# 3-8.net
KiCad netlist of a schematic drawn in Altium Designer
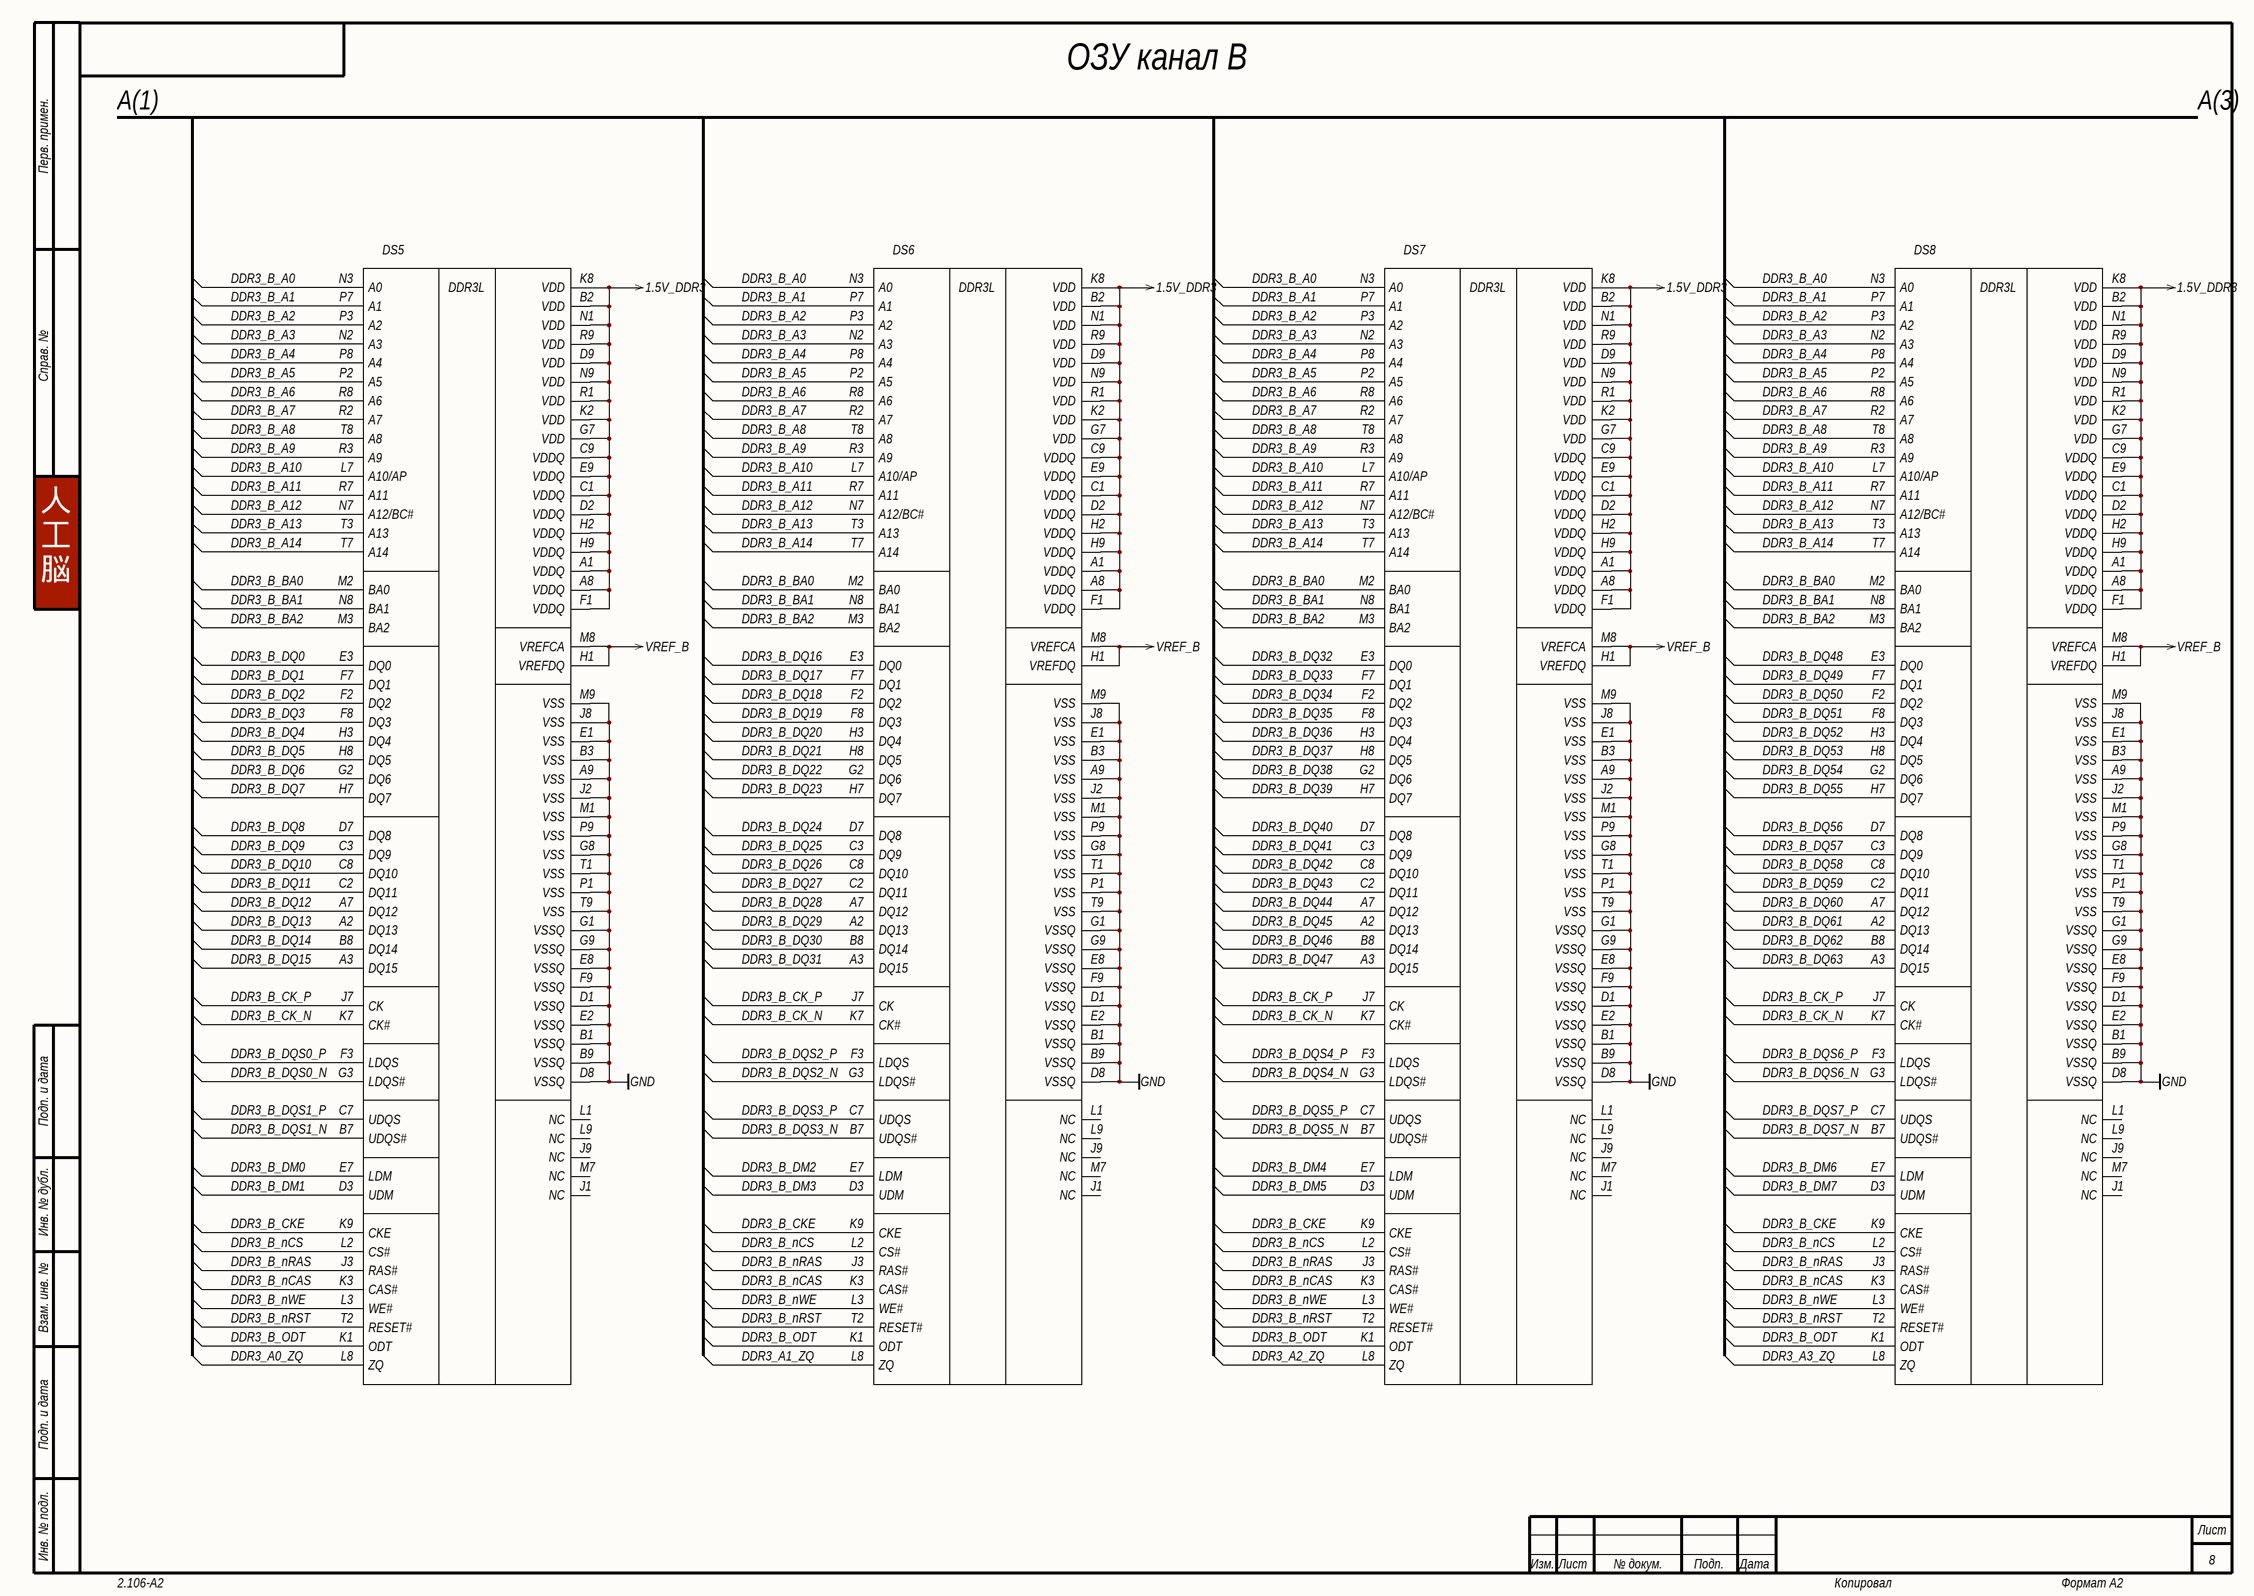
[diagram p0: Э3-8.SchDoc]

(export (version "E")
  (design (tool "Eeschema 10.0.6"))
  (components
    (comp (ref "DS5")
      (value "1")
      (footprint "96-FBGA")
      (description "32 Megx16x8 banks DDR3L SDRAM")
      (fields (field (name "MANUFACTURER") "Micron Technology, Inc."))
      (libsource (lib "Digital") (part "MT41K256M16TW-107IT{colon}P"))
    )
    (comp (ref "DS6")
      (value "1")
      (footprint "96-FBGA")
      (description "32 Megx16x8 banks DDR3L SDRAM")
      (fields (field (name "MANUFACTURER") "Micron Technology, Inc."))
      (libsource (lib "Digital") (part "MT41K256M16TW-107IT{colon}P"))
    )
    (comp (ref "DS7")
      (value "1")
      (footprint "96-FBGA")
      (description "32 Megx16x8 banks DDR3L SDRAM")
      (fields (field (name "MANUFACTURER") "Micron Technology, Inc."))
      (libsource (lib "Digital") (part "MT41K256M16TW-107IT{colon}P"))
    )
    (comp (ref "DS8")
      (value "1")
      (footprint "96-FBGA")
      (description "32 Megx16x8 banks DDR3L SDRAM")
      (fields (field (name "MANUFACTURER") "Micron Technology, Inc."))
      (libsource (lib "Digital") (part "MT41K256M16TW-107IT{colon}P"))
    )
  )
  (nets
    (net (code "1") (name "/DDR3_A0_ZQ") (class "Default")
      (node (ref "DS5") (pin "L8") (pinfunction "ZQ_L8") (pintype "passive"))
    )
    (net (code "2") (name "/DDR3_A1_ZQ") (class "Default")
      (node (ref "DS6") (pin "L8") (pinfunction "ZQ_L8") (pintype "passive"))
    )
    (net (code "3") (name "/DDR3_A2_ZQ") (class "Default")
      (node (ref "DS7") (pin "L8") (pinfunction "ZQ_L8") (pintype "passive"))
    )
    (net (code "4") (name "/DDR3_A3_ZQ") (class "Default")
      (node (ref "DS8") (pin "L8") (pinfunction "ZQ_L8") (pintype "passive"))
    )
    (net (code "5") (name "/DDR3_B_A0") (class "Default")
      (node (ref "DS5") (pin "N3") (pinfunction "A0_N3") (pintype "passive"))
      (node (ref "DS6") (pin "N3") (pinfunction "A0_N3") (pintype "passive"))
      (node (ref "DS7") (pin "N3") (pinfunction "A0_N3") (pintype "passive"))
      (node (ref "DS8") (pin "N3") (pinfunction "A0_N3") (pintype "passive"))
    )
    (net (code "6") (name "/DDR3_B_A1") (class "Default")
      (node (ref "DS5") (pin "P7") (pinfunction "A1_P7") (pintype "passive"))
      (node (ref "DS6") (pin "P7") (pinfunction "A1_P7") (pintype "passive"))
      (node (ref "DS7") (pin "P7") (pinfunction "A1_P7") (pintype "passive"))
      (node (ref "DS8") (pin "P7") (pinfunction "A1_P7") (pintype "passive"))
    )
    (net (code "7") (name "/DDR3_B_A2") (class "Default")
      (node (ref "DS5") (pin "P3") (pinfunction "A2_P3") (pintype "passive"))
      (node (ref "DS6") (pin "P3") (pinfunction "A2_P3") (pintype "passive"))
      (node (ref "DS7") (pin "P3") (pinfunction "A2_P3") (pintype "passive"))
      (node (ref "DS8") (pin "P3") (pinfunction "A2_P3") (pintype "passive"))
    )
    (net (code "8") (name "/DDR3_B_A3") (class "Default")
      (node (ref "DS5") (pin "N2") (pinfunction "A3_N2") (pintype "passive"))
      (node (ref "DS6") (pin "N2") (pinfunction "A3_N2") (pintype "passive"))
      (node (ref "DS7") (pin "N2") (pinfunction "A3_N2") (pintype "passive"))
      (node (ref "DS8") (pin "N2") (pinfunction "A3_N2") (pintype "passive"))
    )
    (net (code "9") (name "/DDR3_B_A4") (class "Default")
      (node (ref "DS5") (pin "P8") (pinfunction "A4_P8") (pintype "passive"))
      (node (ref "DS6") (pin "P8") (pinfunction "A4_P8") (pintype "passive"))
      (node (ref "DS7") (pin "P8") (pinfunction "A4_P8") (pintype "passive"))
      (node (ref "DS8") (pin "P8") (pinfunction "A4_P8") (pintype "passive"))
    )
    (net (code "10") (name "/DDR3_B_A5") (class "Default")
      (node (ref "DS5") (pin "P2") (pinfunction "A5_P2") (pintype "passive"))
      (node (ref "DS6") (pin "P2") (pinfunction "A5_P2") (pintype "passive"))
      (node (ref "DS7") (pin "P2") (pinfunction "A5_P2") (pintype "passive"))
      (node (ref "DS8") (pin "P2") (pinfunction "A5_P2") (pintype "passive"))
    )
    (net (code "11") (name "/DDR3_B_A6") (class "Default")
      (node (ref "DS5") (pin "R8") (pinfunction "A6_R8") (pintype "passive"))
      (node (ref "DS6") (pin "R8") (pinfunction "A6_R8") (pintype "passive"))
      (node (ref "DS7") (pin "R8") (pinfunction "A6_R8") (pintype "passive"))
      (node (ref "DS8") (pin "R8") (pinfunction "A6_R8") (pintype "passive"))
    )
    (net (code "12") (name "/DDR3_B_A7") (class "Default")
      (node (ref "DS5") (pin "R2") (pinfunction "A7_R2") (pintype "passive"))
      (node (ref "DS6") (pin "R2") (pinfunction "A7_R2") (pintype "passive"))
      (node (ref "DS7") (pin "R2") (pinfunction "A7_R2") (pintype "passive"))
      (node (ref "DS8") (pin "R2") (pinfunction "A7_R2") (pintype "passive"))
    )
    (net (code "13") (name "/DDR3_B_A8") (class "Default")
      (node (ref "DS5") (pin "T8") (pinfunction "A8_T8") (pintype "passive"))
      (node (ref "DS6") (pin "T8") (pinfunction "A8_T8") (pintype "passive"))
      (node (ref "DS7") (pin "T8") (pinfunction "A8_T8") (pintype "passive"))
      (node (ref "DS8") (pin "T8") (pinfunction "A8_T8") (pintype "passive"))
    )
    (net (code "14") (name "/DDR3_B_A9") (class "Default")
      (node (ref "DS5") (pin "R3") (pinfunction "A9_R3") (pintype "passive"))
      (node (ref "DS6") (pin "R3") (pinfunction "A9_R3") (pintype "passive"))
      (node (ref "DS7") (pin "R3") (pinfunction "A9_R3") (pintype "passive"))
      (node (ref "DS8") (pin "R3") (pinfunction "A9_R3") (pintype "passive"))
    )
    (net (code "15") (name "/DDR3_B_A10") (class "Default")
      (node (ref "DS5") (pin "L7") (pinfunction "A10/AP_L7") (pintype "passive"))
      (node (ref "DS6") (pin "L7") (pinfunction "A10/AP_L7") (pintype "passive"))
      (node (ref "DS7") (pin "L7") (pinfunction "A10/AP_L7") (pintype "passive"))
      (node (ref "DS8") (pin "L7") (pinfunction "A10/AP_L7") (pintype "passive"))
    )
    (net (code "16") (name "/DDR3_B_A11") (class "Default")
      (node (ref "DS5") (pin "R7") (pinfunction "A11_R7") (pintype "passive"))
      (node (ref "DS6") (pin "R7") (pinfunction "A11_R7") (pintype "passive"))
      (node (ref "DS7") (pin "R7") (pinfunction "A11_R7") (pintype "passive"))
      (node (ref "DS8") (pin "R7") (pinfunction "A11_R7") (pintype "passive"))
    )
    (net (code "17") (name "/DDR3_B_A12") (class "Default")
      (node (ref "DS5") (pin "N7") (pinfunction "A12/BC#_N7") (pintype "passive"))
      (node (ref "DS6") (pin "N7") (pinfunction "A12/BC#_N7") (pintype "passive"))
      (node (ref "DS7") (pin "N7") (pinfunction "A12/BC#_N7") (pintype "passive"))
      (node (ref "DS8") (pin "N7") (pinfunction "A12/BC#_N7") (pintype "passive"))
    )
    (net (code "18") (name "/DDR3_B_A13") (class "Default")
      (node (ref "DS5") (pin "T3") (pinfunction "A13_T3") (pintype "passive"))
      (node (ref "DS6") (pin "T3") (pinfunction "A13_T3") (pintype "passive"))
      (node (ref "DS7") (pin "T3") (pinfunction "A13_T3") (pintype "passive"))
      (node (ref "DS8") (pin "T3") (pinfunction "A13_T3") (pintype "passive"))
    )
    (net (code "19") (name "/DDR3_B_A14") (class "Default")
      (node (ref "DS5") (pin "T7") (pinfunction "A14_T7") (pintype "passive"))
      (node (ref "DS6") (pin "T7") (pinfunction "A14_T7") (pintype "passive"))
      (node (ref "DS7") (pin "T7") (pinfunction "A14_T7") (pintype "passive"))
      (node (ref "DS8") (pin "T7") (pinfunction "A14_T7") (pintype "passive"))
    )
    (net (code "20") (name "/DDR3_B_BA0") (class "Default")
      (node (ref "DS5") (pin "M2") (pinfunction "BA0_M2") (pintype "passive"))
      (node (ref "DS6") (pin "M2") (pinfunction "BA0_M2") (pintype "passive"))
      (node (ref "DS7") (pin "M2") (pinfunction "BA0_M2") (pintype "passive"))
      (node (ref "DS8") (pin "M2") (pinfunction "BA0_M2") (pintype "passive"))
    )
    (net (code "21") (name "/DDR3_B_BA1") (class "Default")
      (node (ref "DS5") (pin "N8") (pinfunction "BA1_N8") (pintype "passive"))
      (node (ref "DS6") (pin "N8") (pinfunction "BA1_N8") (pintype "passive"))
      (node (ref "DS7") (pin "N8") (pinfunction "BA1_N8") (pintype "passive"))
      (node (ref "DS8") (pin "N8") (pinfunction "BA1_N8") (pintype "passive"))
    )
    (net (code "22") (name "/DDR3_B_BA2") (class "Default")
      (node (ref "DS5") (pin "M3") (pinfunction "BA2_M3") (pintype "passive"))
      (node (ref "DS6") (pin "M3") (pinfunction "BA2_M3") (pintype "passive"))
      (node (ref "DS7") (pin "M3") (pinfunction "BA2_M3") (pintype "passive"))
      (node (ref "DS8") (pin "M3") (pinfunction "BA2_M3") (pintype "passive"))
    )
    (net (code "23") (name "/DDR3_B_CKE") (class "Default")
      (node (ref "DS5") (pin "K9") (pinfunction "CKE_K9") (pintype "passive"))
      (node (ref "DS6") (pin "K9") (pinfunction "CKE_K9") (pintype "passive"))
      (node (ref "DS7") (pin "K9") (pinfunction "CKE_K9") (pintype "passive"))
      (node (ref "DS8") (pin "K9") (pinfunction "CKE_K9") (pintype "passive"))
    )
    (net (code "24") (name "/DDR3_B_CK_N") (class "Default")
      (node (ref "DS5") (pin "K7") (pinfunction "CK#_K7") (pintype "passive"))
      (node (ref "DS6") (pin "K7") (pinfunction "CK#_K7") (pintype "passive"))
      (node (ref "DS7") (pin "K7") (pinfunction "CK#_K7") (pintype "passive"))
      (node (ref "DS8") (pin "K7") (pinfunction "CK#_K7") (pintype "passive"))
    )
    (net (code "25") (name "/DDR3_B_CK_P") (class "Default")
      (node (ref "DS5") (pin "J7") (pinfunction "CK_J7") (pintype "passive"))
      (node (ref "DS6") (pin "J7") (pinfunction "CK_J7") (pintype "passive"))
      (node (ref "DS7") (pin "J7") (pinfunction "CK_J7") (pintype "passive"))
      (node (ref "DS8") (pin "J7") (pinfunction "CK_J7") (pintype "passive"))
    )
    (net (code "26") (name "/DDR3_B_DM0") (class "Default")
      (node (ref "DS5") (pin "E7") (pinfunction "LDM_E7") (pintype "passive"))
    )
    (net (code "27") (name "/DDR3_B_DM1") (class "Default")
      (node (ref "DS5") (pin "D3") (pinfunction "UDM_D3") (pintype "passive"))
    )
    (net (code "28") (name "/DDR3_B_DM2") (class "Default")
      (node (ref "DS6") (pin "E7") (pinfunction "LDM_E7") (pintype "passive"))
    )
    (net (code "29") (name "/DDR3_B_DM3") (class "Default")
      (node (ref "DS6") (pin "D3") (pinfunction "UDM_D3") (pintype "passive"))
    )
    (net (code "30") (name "/DDR3_B_DM4") (class "Default")
      (node (ref "DS7") (pin "E7") (pinfunction "LDM_E7") (pintype "passive"))
    )
    (net (code "31") (name "/DDR3_B_DM5") (class "Default")
      (node (ref "DS7") (pin "D3") (pinfunction "UDM_D3") (pintype "passive"))
    )
    (net (code "32") (name "/DDR3_B_DM6") (class "Default")
      (node (ref "DS8") (pin "E7") (pinfunction "LDM_E7") (pintype "passive"))
    )
    (net (code "33") (name "/DDR3_B_DM7") (class "Default")
      (node (ref "DS8") (pin "D3") (pinfunction "UDM_D3") (pintype "passive"))
    )
    (net (code "34") (name "/DDR3_B_DQ0") (class "Default")
      (node (ref "DS5") (pin "E3") (pinfunction "DQ0_E3") (pintype "passive"))
    )
    (net (code "35") (name "/DDR3_B_DQ1") (class "Default")
      (node (ref "DS5") (pin "F7") (pinfunction "DQ1_F7") (pintype "passive"))
    )
    (net (code "36") (name "/DDR3_B_DQ2") (class "Default")
      (node (ref "DS5") (pin "F2") (pinfunction "DQ2_F2") (pintype "passive"))
    )
    (net (code "37") (name "/DDR3_B_DQ3") (class "Default")
      (node (ref "DS5") (pin "F8") (pinfunction "DQ3_F8") (pintype "passive"))
    )
    (net (code "38") (name "/DDR3_B_DQ4") (class "Default")
      (node (ref "DS5") (pin "H3") (pinfunction "DQ4_H3") (pintype "passive"))
    )
    (net (code "39") (name "/DDR3_B_DQ5") (class "Default")
      (node (ref "DS5") (pin "H8") (pinfunction "DQ5_H8") (pintype "passive"))
    )
    (net (code "40") (name "/DDR3_B_DQ6") (class "Default")
      (node (ref "DS5") (pin "G2") (pinfunction "DQ6_G2") (pintype "passive"))
    )
    (net (code "41") (name "/DDR3_B_DQ7") (class "Default")
      (node (ref "DS5") (pin "H7") (pinfunction "DQ7_H7") (pintype "passive"))
    )
    (net (code "42") (name "/DDR3_B_DQ8") (class "Default")
      (node (ref "DS5") (pin "D7") (pinfunction "DQ8_D7") (pintype "passive"))
    )
    (net (code "43") (name "/DDR3_B_DQ9") (class "Default")
      (node (ref "DS5") (pin "C3") (pinfunction "DQ9_C3") (pintype "passive"))
    )
    (net (code "44") (name "/DDR3_B_DQ10") (class "Default")
      (node (ref "DS5") (pin "C8") (pinfunction "DQ10_C8") (pintype "passive"))
    )
    (net (code "45") (name "/DDR3_B_DQ11") (class "Default")
      (node (ref "DS5") (pin "C2") (pinfunction "DQ11_C2") (pintype "passive"))
    )
    (net (code "46") (name "/DDR3_B_DQ12") (class "Default")
      (node (ref "DS5") (pin "A7") (pinfunction "DQ12_A7") (pintype "passive"))
    )
    (net (code "47") (name "/DDR3_B_DQ13") (class "Default")
      (node (ref "DS5") (pin "A2") (pinfunction "DQ13_A2") (pintype "passive"))
    )
    (net (code "48") (name "/DDR3_B_DQ14") (class "Default")
      (node (ref "DS5") (pin "B8") (pinfunction "DQ14_B8") (pintype "passive"))
    )
    (net (code "49") (name "/DDR3_B_DQ15") (class "Default")
      (node (ref "DS5") (pin "A3") (pinfunction "DQ15_A3") (pintype "passive"))
    )
    (net (code "50") (name "/DDR3_B_DQ16") (class "Default")
      (node (ref "DS6") (pin "E3") (pinfunction "DQ0_E3") (pintype "passive"))
    )
    (net (code "51") (name "/DDR3_B_DQ17") (class "Default")
      (node (ref "DS6") (pin "F7") (pinfunction "DQ1_F7") (pintype "passive"))
    )
    (net (code "52") (name "/DDR3_B_DQ18") (class "Default")
      (node (ref "DS6") (pin "F2") (pinfunction "DQ2_F2") (pintype "passive"))
    )
    (net (code "53") (name "/DDR3_B_DQ19") (class "Default")
      (node (ref "DS6") (pin "F8") (pinfunction "DQ3_F8") (pintype "passive"))
    )
    (net (code "54") (name "/DDR3_B_DQ20") (class "Default")
      (node (ref "DS6") (pin "H3") (pinfunction "DQ4_H3") (pintype "passive"))
    )
    (net (code "55") (name "/DDR3_B_DQ21") (class "Default")
      (node (ref "DS6") (pin "H8") (pinfunction "DQ5_H8") (pintype "passive"))
    )
    (net (code "56") (name "/DDR3_B_DQ22") (class "Default")
      (node (ref "DS6") (pin "G2") (pinfunction "DQ6_G2") (pintype "passive"))
    )
    (net (code "57") (name "/DDR3_B_DQ23") (class "Default")
      (node (ref "DS6") (pin "H7") (pinfunction "DQ7_H7") (pintype "passive"))
    )
    (net (code "58") (name "/DDR3_B_DQ24") (class "Default")
      (node (ref "DS6") (pin "D7") (pinfunction "DQ8_D7") (pintype "passive"))
    )
    (net (code "59") (name "/DDR3_B_DQ25") (class "Default")
      (node (ref "DS6") (pin "C3") (pinfunction "DQ9_C3") (pintype "passive"))
    )
    (net (code "60") (name "/DDR3_B_DQ26") (class "Default")
      (node (ref "DS6") (pin "C8") (pinfunction "DQ10_C8") (pintype "passive"))
    )
    (net (code "61") (name "/DDR3_B_DQ27") (class "Default")
      (node (ref "DS6") (pin "C2") (pinfunction "DQ11_C2") (pintype "passive"))
    )
    (net (code "62") (name "/DDR3_B_DQ28") (class "Default")
      (node (ref "DS6") (pin "A7") (pinfunction "DQ12_A7") (pintype "passive"))
    )
    (net (code "63") (name "/DDR3_B_DQ29") (class "Default")
      (node (ref "DS6") (pin "A2") (pinfunction "DQ13_A2") (pintype "passive"))
    )
    (net (code "64") (name "/DDR3_B_DQ30") (class "Default")
      (node (ref "DS6") (pin "B8") (pinfunction "DQ14_B8") (pintype "passive"))
    )
    (net (code "65") (name "/DDR3_B_DQ31") (class "Default")
      (node (ref "DS6") (pin "A3") (pinfunction "DQ15_A3") (pintype "passive"))
    )
    (net (code "66") (name "/DDR3_B_DQ32") (class "Default")
      (node (ref "DS7") (pin "E3") (pinfunction "DQ0_E3") (pintype "passive"))
    )
    (net (code "67") (name "/DDR3_B_DQ33") (class "Default")
      (node (ref "DS7") (pin "F7") (pinfunction "DQ1_F7") (pintype "passive"))
    )
    (net (code "68") (name "/DDR3_B_DQ34") (class "Default")
      (node (ref "DS7") (pin "F2") (pinfunction "DQ2_F2") (pintype "passive"))
    )
    (net (code "69") (name "/DDR3_B_DQ35") (class "Default")
      (node (ref "DS7") (pin "F8") (pinfunction "DQ3_F8") (pintype "passive"))
    )
    (net (code "70") (name "/DDR3_B_DQ36") (class "Default")
      (node (ref "DS7") (pin "H3") (pinfunction "DQ4_H3") (pintype "passive"))
    )
    (net (code "71") (name "/DDR3_B_DQ37") (class "Default")
      (node (ref "DS7") (pin "H8") (pinfunction "DQ5_H8") (pintype "passive"))
    )
    (net (code "72") (name "/DDR3_B_DQ38") (class "Default")
      (node (ref "DS7") (pin "G2") (pinfunction "DQ6_G2") (pintype "passive"))
    )
    (net (code "73") (name "/DDR3_B_DQ39") (class "Default")
      (node (ref "DS7") (pin "H7") (pinfunction "DQ7_H7") (pintype "passive"))
    )
    (net (code "74") (name "/DDR3_B_DQ40") (class "Default")
      (node (ref "DS7") (pin "D7") (pinfunction "DQ8_D7") (pintype "passive"))
    )
    (net (code "75") (name "/DDR3_B_DQ41") (class "Default")
      (node (ref "DS7") (pin "C3") (pinfunction "DQ9_C3") (pintype "passive"))
    )
    (net (code "76") (name "/DDR3_B_DQ42") (class "Default")
      (node (ref "DS7") (pin "C8") (pinfunction "DQ10_C8") (pintype "passive"))
    )
    (net (code "77") (name "/DDR3_B_DQ43") (class "Default")
      (node (ref "DS7") (pin "C2") (pinfunction "DQ11_C2") (pintype "passive"))
    )
    (net (code "78") (name "/DDR3_B_DQ44") (class "Default")
      (node (ref "DS7") (pin "A7") (pinfunction "DQ12_A7") (pintype "passive"))
    )
    (net (code "79") (name "/DDR3_B_DQ45") (class "Default")
      (node (ref "DS7") (pin "A2") (pinfunction "DQ13_A2") (pintype "passive"))
    )
    (net (code "80") (name "/DDR3_B_DQ46") (class "Default")
      (node (ref "DS7") (pin "B8") (pinfunction "DQ14_B8") (pintype "passive"))
    )
    (net (code "81") (name "/DDR3_B_DQ47") (class "Default")
      (node (ref "DS7") (pin "A3") (pinfunction "DQ15_A3") (pintype "passive"))
    )
    (net (code "82") (name "/DDR3_B_DQ48") (class "Default")
      (node (ref "DS8") (pin "E3") (pinfunction "DQ0_E3") (pintype "passive"))
    )
    (net (code "83") (name "/DDR3_B_DQ49") (class "Default")
      (node (ref "DS8") (pin "F7") (pinfunction "DQ1_F7") (pintype "passive"))
    )
    (net (code "84") (name "/DDR3_B_DQ50") (class "Default")
      (node (ref "DS8") (pin "F2") (pinfunction "DQ2_F2") (pintype "passive"))
    )
    (net (code "85") (name "/DDR3_B_DQ51") (class "Default")
      (node (ref "DS8") (pin "F8") (pinfunction "DQ3_F8") (pintype "passive"))
    )
    (net (code "86") (name "/DDR3_B_DQ52") (class "Default")
      (node (ref "DS8") (pin "H3") (pinfunction "DQ4_H3") (pintype "passive"))
    )
    (net (code "87") (name "/DDR3_B_DQ53") (class "Default")
      (node (ref "DS8") (pin "H8") (pinfunction "DQ5_H8") (pintype "passive"))
    )
    (net (code "88") (name "/DDR3_B_DQ54") (class "Default")
      (node (ref "DS8") (pin "G2") (pinfunction "DQ6_G2") (pintype "passive"))
    )
    (net (code "89") (name "/DDR3_B_DQ55") (class "Default")
      (node (ref "DS8") (pin "H7") (pinfunction "DQ7_H7") (pintype "passive"))
    )
    (net (code "90") (name "/DDR3_B_DQ56") (class "Default")
      (node (ref "DS8") (pin "D7") (pinfunction "DQ8_D7") (pintype "passive"))
    )
    (net (code "91") (name "/DDR3_B_DQ57") (class "Default")
      (node (ref "DS8") (pin "C3") (pinfunction "DQ9_C3") (pintype "passive"))
    )
    (net (code "92") (name "/DDR3_B_DQ58") (class "Default")
      (node (ref "DS8") (pin "C8") (pinfunction "DQ10_C8") (pintype "passive"))
    )
    (net (code "93") (name "/DDR3_B_DQ59") (class "Default")
      (node (ref "DS8") (pin "C2") (pinfunction "DQ11_C2") (pintype "passive"))
    )
    (net (code "94") (name "/DDR3_B_DQ60") (class "Default")
      (node (ref "DS8") (pin "A7") (pinfunction "DQ12_A7") (pintype "passive"))
    )
    (net (code "95") (name "/DDR3_B_DQ61") (class "Default")
      (node (ref "DS8") (pin "A2") (pinfunction "DQ13_A2") (pintype "passive"))
    )
    (net (code "96") (name "/DDR3_B_DQ62") (class "Default")
      (node (ref "DS8") (pin "B8") (pinfunction "DQ14_B8") (pintype "passive"))
    )
    (net (code "97") (name "/DDR3_B_DQ63") (class "Default")
      (node (ref "DS8") (pin "A3") (pinfunction "DQ15_A3") (pintype "passive"))
    )
    (net (code "98") (name "/DDR3_B_DQS0_N") (class "Default")
      (node (ref "DS5") (pin "G3") (pinfunction "LDQS#_G3") (pintype "passive"))
    )
    (net (code "99") (name "/DDR3_B_DQS0_P") (class "Default")
      (node (ref "DS5") (pin "F3") (pinfunction "LDQS_F3") (pintype "passive"))
    )
    (net (code "100") (name "/DDR3_B_DQS1_N") (class "Default")
      (node (ref "DS5") (pin "B7") (pinfunction "UDQS#_B7") (pintype "passive"))
    )
    (net (code "101") (name "/DDR3_B_DQS1_P") (class "Default")
      (node (ref "DS5") (pin "C7") (pinfunction "UDQS_C7") (pintype "passive"))
    )
    (net (code "102") (name "/DDR3_B_DQS2_N") (class "Default")
      (node (ref "DS6") (pin "G3") (pinfunction "LDQS#_G3") (pintype "passive"))
    )
    (net (code "103") (name "/DDR3_B_DQS2_P") (class "Default")
      (node (ref "DS6") (pin "F3") (pinfunction "LDQS_F3") (pintype "passive"))
    )
    (net (code "104") (name "/DDR3_B_DQS3_N") (class "Default")
      (node (ref "DS6") (pin "B7") (pinfunction "UDQS#_B7") (pintype "passive"))
    )
    (net (code "105") (name "/DDR3_B_DQS3_P") (class "Default")
      (node (ref "DS6") (pin "C7") (pinfunction "UDQS_C7") (pintype "passive"))
    )
    (net (code "106") (name "/DDR3_B_DQS4_N") (class "Default")
      (node (ref "DS7") (pin "G3") (pinfunction "LDQS#_G3") (pintype "passive"))
    )
    (net (code "107") (name "/DDR3_B_DQS4_P") (class "Default")
      (node (ref "DS7") (pin "F3") (pinfunction "LDQS_F3") (pintype "passive"))
    )
    (net (code "108") (name "/DDR3_B_DQS5_N") (class "Default")
      (node (ref "DS7") (pin "B7") (pinfunction "UDQS#_B7") (pintype "passive"))
    )
    (net (code "109") (name "/DDR3_B_DQS5_P") (class "Default")
      (node (ref "DS7") (pin "C7") (pinfunction "UDQS_C7") (pintype "passive"))
    )
    (net (code "110") (name "/DDR3_B_DQS6_N") (class "Default")
      (node (ref "DS8") (pin "G3") (pinfunction "LDQS#_G3") (pintype "passive"))
    )
    (net (code "111") (name "/DDR3_B_DQS6_P") (class "Default")
      (node (ref "DS8") (pin "F3") (pinfunction "LDQS_F3") (pintype "passive"))
    )
    (net (code "112") (name "/DDR3_B_DQS7_N") (class "Default")
      (node (ref "DS8") (pin "B7") (pinfunction "UDQS#_B7") (pintype "passive"))
    )
    (net (code "113") (name "/DDR3_B_DQS7_P") (class "Default")
      (node (ref "DS8") (pin "C7") (pinfunction "UDQS_C7") (pintype "passive"))
    )
    (net (code "114") (name "/DDR3_B_ODT") (class "Default")
      (node (ref "DS5") (pin "K1") (pinfunction "ODT_K1") (pintype "passive"))
      (node (ref "DS6") (pin "K1") (pinfunction "ODT_K1") (pintype "passive"))
      (node (ref "DS7") (pin "K1") (pinfunction "ODT_K1") (pintype "passive"))
      (node (ref "DS8") (pin "K1") (pinfunction "ODT_K1") (pintype "passive"))
    )
    (net (code "115") (name "/DDR3_B_nCAS") (class "Default")
      (node (ref "DS5") (pin "K3") (pinfunction "CAS#_K3") (pintype "passive"))
      (node (ref "DS6") (pin "K3") (pinfunction "CAS#_K3") (pintype "passive"))
      (node (ref "DS7") (pin "K3") (pinfunction "CAS#_K3") (pintype "passive"))
      (node (ref "DS8") (pin "K3") (pinfunction "CAS#_K3") (pintype "passive"))
    )
    (net (code "116") (name "/DDR3_B_nCS") (class "Default")
      (node (ref "DS5") (pin "L2") (pinfunction "CS#_L2") (pintype "passive"))
      (node (ref "DS6") (pin "L2") (pinfunction "CS#_L2") (pintype "passive"))
      (node (ref "DS7") (pin "L2") (pinfunction "CS#_L2") (pintype "passive"))
      (node (ref "DS8") (pin "L2") (pinfunction "CS#_L2") (pintype "passive"))
    )
    (net (code "117") (name "/DDR3_B_nRAS") (class "Default")
      (node (ref "DS5") (pin "J3") (pinfunction "RAS#_J3") (pintype "passive"))
      (node (ref "DS6") (pin "J3") (pinfunction "RAS#_J3") (pintype "passive"))
      (node (ref "DS7") (pin "J3") (pinfunction "RAS#_J3") (pintype "passive"))
      (node (ref "DS8") (pin "J3") (pinfunction "RAS#_J3") (pintype "passive"))
    )
    (net (code "118") (name "/DDR3_B_nRST") (class "Default")
      (node (ref "DS5") (pin "T2") (pinfunction "RESET#_T2") (pintype "passive"))
      (node (ref "DS6") (pin "T2") (pinfunction "RESET#_T2") (pintype "passive"))
      (node (ref "DS7") (pin "T2") (pinfunction "RESET#_T2") (pintype "passive"))
      (node (ref "DS8") (pin "T2") (pinfunction "RESET#_T2") (pintype "passive"))
    )
    (net (code "119") (name "/DDR3_B_nWE") (class "Default")
      (node (ref "DS5") (pin "L3") (pinfunction "WE#_L3") (pintype "passive"))
      (node (ref "DS6") (pin "L3") (pinfunction "WE#_L3") (pintype "passive"))
      (node (ref "DS7") (pin "L3") (pinfunction "WE#_L3") (pintype "passive"))
      (node (ref "DS8") (pin "L3") (pinfunction "WE#_L3") (pintype "passive"))
    )
    (net (code "120") (name "1.5V_DDR3") (class "Default")
      (node (ref "DS5") (pin "A1") (pinfunction "VDDQ_A1") (pintype "passive"))
      (node (ref "DS5") (pin "A8") (pinfunction "VDDQ_A8") (pintype "passive"))
      (node (ref "DS5") (pin "B2") (pinfunction "VDD_B2") (pintype "passive"))
      (node (ref "DS5") (pin "C1") (pinfunction "VDDQ_C1") (pintype "passive"))
      (node (ref "DS5") (pin "C9") (pinfunction "VDDQ_C9") (pintype "passive"))
      (node (ref "DS5") (pin "D2") (pinfunction "VDDQ_D2") (pintype "passive"))
      (node (ref "DS5") (pin "D9") (pinfunction "VDD_D9") (pintype "passive"))
      (node (ref "DS5") (pin "E9") (pinfunction "VDDQ_E9") (pintype "passive"))
      (node (ref "DS5") (pin "F1") (pinfunction "VDDQ_F1") (pintype "passive"))
      (node (ref "DS5") (pin "G7") (pinfunction "VDD_G7") (pintype "passive"))
      (node (ref "DS5") (pin "H2") (pinfunction "VDDQ_H2") (pintype "passive"))
      (node (ref "DS5") (pin "H9") (pinfunction "VDDQ_H9") (pintype "passive"))
      (node (ref "DS5") (pin "K2") (pinfunction "VDD_K2") (pintype "passive"))
      (node (ref "DS5") (pin "K8") (pinfunction "VDD_K8") (pintype "passive"))
      (node (ref "DS5") (pin "N1") (pinfunction "VDD_N1") (pintype "passive"))
      (node (ref "DS5") (pin "N9") (pinfunction "VDD_N9") (pintype "passive"))
      (node (ref "DS5") (pin "R1") (pinfunction "VDD_R1") (pintype "passive"))
      (node (ref "DS5") (pin "R9") (pinfunction "VDD_R9") (pintype "passive"))
      (node (ref "DS6") (pin "A1") (pinfunction "VDDQ_A1") (pintype "passive"))
      (node (ref "DS6") (pin "A8") (pinfunction "VDDQ_A8") (pintype "passive"))
      (node (ref "DS6") (pin "B2") (pinfunction "VDD_B2") (pintype "passive"))
      (node (ref "DS6") (pin "C1") (pinfunction "VDDQ_C1") (pintype "passive"))
      (node (ref "DS6") (pin "C9") (pinfunction "VDDQ_C9") (pintype "passive"))
      (node (ref "DS6") (pin "D2") (pinfunction "VDDQ_D2") (pintype "passive"))
      (node (ref "DS6") (pin "D9") (pinfunction "VDD_D9") (pintype "passive"))
      (node (ref "DS6") (pin "E9") (pinfunction "VDDQ_E9") (pintype "passive"))
      (node (ref "DS6") (pin "F1") (pinfunction "VDDQ_F1") (pintype "passive"))
      (node (ref "DS6") (pin "G7") (pinfunction "VDD_G7") (pintype "passive"))
      (node (ref "DS6") (pin "H2") (pinfunction "VDDQ_H2") (pintype "passive"))
      (node (ref "DS6") (pin "H9") (pinfunction "VDDQ_H9") (pintype "passive"))
      (node (ref "DS6") (pin "K2") (pinfunction "VDD_K2") (pintype "passive"))
      (node (ref "DS6") (pin "K8") (pinfunction "VDD_K8") (pintype "passive"))
      (node (ref "DS6") (pin "N1") (pinfunction "VDD_N1") (pintype "passive"))
      (node (ref "DS6") (pin "N9") (pinfunction "VDD_N9") (pintype "passive"))
      (node (ref "DS6") (pin "R1") (pinfunction "VDD_R1") (pintype "passive"))
      (node (ref "DS6") (pin "R9") (pinfunction "VDD_R9") (pintype "passive"))
      (node (ref "DS7") (pin "A1") (pinfunction "VDDQ_A1") (pintype "passive"))
      (node (ref "DS7") (pin "A8") (pinfunction "VDDQ_A8") (pintype "passive"))
      (node (ref "DS7") (pin "B2") (pinfunction "VDD_B2") (pintype "passive"))
      (node (ref "DS7") (pin "C1") (pinfunction "VDDQ_C1") (pintype "passive"))
      (node (ref "DS7") (pin "C9") (pinfunction "VDDQ_C9") (pintype "passive"))
      (node (ref "DS7") (pin "D2") (pinfunction "VDDQ_D2") (pintype "passive"))
      (node (ref "DS7") (pin "D9") (pinfunction "VDD_D9") (pintype "passive"))
      (node (ref "DS7") (pin "E9") (pinfunction "VDDQ_E9") (pintype "passive"))
      (node (ref "DS7") (pin "F1") (pinfunction "VDDQ_F1") (pintype "passive"))
      (node (ref "DS7") (pin "G7") (pinfunction "VDD_G7") (pintype "passive"))
      (node (ref "DS7") (pin "H2") (pinfunction "VDDQ_H2") (pintype "passive"))
      (node (ref "DS7") (pin "H9") (pinfunction "VDDQ_H9") (pintype "passive"))
      (node (ref "DS7") (pin "K2") (pinfunction "VDD_K2") (pintype "passive"))
      (node (ref "DS7") (pin "K8") (pinfunction "VDD_K8") (pintype "passive"))
      (node (ref "DS7") (pin "N1") (pinfunction "VDD_N1") (pintype "passive"))
      (node (ref "DS7") (pin "N9") (pinfunction "VDD_N9") (pintype "passive"))
      (node (ref "DS7") (pin "R1") (pinfunction "VDD_R1") (pintype "passive"))
      (node (ref "DS7") (pin "R9") (pinfunction "VDD_R9") (pintype "passive"))
      (node (ref "DS8") (pin "A1") (pinfunction "VDDQ_A1") (pintype "passive"))
      (node (ref "DS8") (pin "A8") (pinfunction "VDDQ_A8") (pintype "passive"))
      (node (ref "DS8") (pin "B2") (pinfunction "VDD_B2") (pintype "passive"))
      (node (ref "DS8") (pin "C1") (pinfunction "VDDQ_C1") (pintype "passive"))
      (node (ref "DS8") (pin "C9") (pinfunction "VDDQ_C9") (pintype "passive"))
      (node (ref "DS8") (pin "D2") (pinfunction "VDDQ_D2") (pintype "passive"))
      (node (ref "DS8") (pin "D9") (pinfunction "VDD_D9") (pintype "passive"))
      (node (ref "DS8") (pin "E9") (pinfunction "VDDQ_E9") (pintype "passive"))
      (node (ref "DS8") (pin "F1") (pinfunction "VDDQ_F1") (pintype "passive"))
      (node (ref "DS8") (pin "G7") (pinfunction "VDD_G7") (pintype "passive"))
      (node (ref "DS8") (pin "H2") (pinfunction "VDDQ_H2") (pintype "passive"))
      (node (ref "DS8") (pin "H9") (pinfunction "VDDQ_H9") (pintype "passive"))
      (node (ref "DS8") (pin "K2") (pinfunction "VDD_K2") (pintype "passive"))
      (node (ref "DS8") (pin "K8") (pinfunction "VDD_K8") (pintype "passive"))
      (node (ref "DS8") (pin "N1") (pinfunction "VDD_N1") (pintype "passive"))
      (node (ref "DS8") (pin "N9") (pinfunction "VDD_N9") (pintype "passive"))
      (node (ref "DS8") (pin "R1") (pinfunction "VDD_R1") (pintype "passive"))
      (node (ref "DS8") (pin "R9") (pinfunction "VDD_R9") (pintype "passive"))
    )
    (net (code "121") (name "GND") (class "Default")
      (node (ref "DS5") (pin "A9") (pinfunction "VSS_A9") (pintype "passive"))
      (node (ref "DS5") (pin "B1") (pinfunction "VSSQ_B1") (pintype "passive"))
      (node (ref "DS5") (pin "B3") (pinfunction "VSS_B3") (pintype "passive"))
      (node (ref "DS5") (pin "B9") (pinfunction "VSSQ_B9") (pintype "passive"))
      (node (ref "DS5") (pin "D1") (pinfunction "VSSQ_D1") (pintype "passive"))
      (node (ref "DS5") (pin "D8") (pinfunction "VSSQ_D8") (pintype "passive"))
      (node (ref "DS5") (pin "E1") (pinfunction "VSS_E1") (pintype "passive"))
      (node (ref "DS5") (pin "E2") (pinfunction "VSSQ_E2") (pintype "passive"))
      (node (ref "DS5") (pin "E8") (pinfunction "VSSQ_E8") (pintype "passive"))
      (node (ref "DS5") (pin "F9") (pinfunction "VSSQ_F9") (pintype "passive"))
      (node (ref "DS5") (pin "G1") (pinfunction "VSSQ_G1") (pintype "passive"))
      (node (ref "DS5") (pin "G8") (pinfunction "VSS_G8") (pintype "passive"))
      (node (ref "DS5") (pin "G9") (pinfunction "VSSQ_G9") (pintype "passive"))
      (node (ref "DS5") (pin "J2") (pinfunction "VSS_J2") (pintype "passive"))
      (node (ref "DS5") (pin "J8") (pinfunction "VSS_J8") (pintype "passive"))
      (node (ref "DS5") (pin "M1") (pinfunction "VSS_M1") (pintype "passive"))
      (node (ref "DS5") (pin "M9") (pinfunction "VSS_M9") (pintype "passive"))
      (node (ref "DS5") (pin "P1") (pinfunction "VSS_P1") (pintype "passive"))
      (node (ref "DS5") (pin "P9") (pinfunction "VSS_P9") (pintype "passive"))
      (node (ref "DS5") (pin "T1") (pinfunction "VSS_T1") (pintype "passive"))
      (node (ref "DS5") (pin "T9") (pinfunction "VSS_T9") (pintype "passive"))
      (node (ref "DS6") (pin "A9") (pinfunction "VSS_A9") (pintype "passive"))
      (node (ref "DS6") (pin "B1") (pinfunction "VSSQ_B1") (pintype "passive"))
      (node (ref "DS6") (pin "B3") (pinfunction "VSS_B3") (pintype "passive"))
      (node (ref "DS6") (pin "B9") (pinfunction "VSSQ_B9") (pintype "passive"))
      (node (ref "DS6") (pin "D1") (pinfunction "VSSQ_D1") (pintype "passive"))
      (node (ref "DS6") (pin "D8") (pinfunction "VSSQ_D8") (pintype "passive"))
      (node (ref "DS6") (pin "E1") (pinfunction "VSS_E1") (pintype "passive"))
      (node (ref "DS6") (pin "E2") (pinfunction "VSSQ_E2") (pintype "passive"))
      (node (ref "DS6") (pin "E8") (pinfunction "VSSQ_E8") (pintype "passive"))
      (node (ref "DS6") (pin "F9") (pinfunction "VSSQ_F9") (pintype "passive"))
      (node (ref "DS6") (pin "G1") (pinfunction "VSSQ_G1") (pintype "passive"))
      (node (ref "DS6") (pin "G8") (pinfunction "VSS_G8") (pintype "passive"))
      (node (ref "DS6") (pin "G9") (pinfunction "VSSQ_G9") (pintype "passive"))
      (node (ref "DS6") (pin "J2") (pinfunction "VSS_J2") (pintype "passive"))
      (node (ref "DS6") (pin "J8") (pinfunction "VSS_J8") (pintype "passive"))
      (node (ref "DS6") (pin "M1") (pinfunction "VSS_M1") (pintype "passive"))
      (node (ref "DS6") (pin "M9") (pinfunction "VSS_M9") (pintype "passive"))
      (node (ref "DS6") (pin "P1") (pinfunction "VSS_P1") (pintype "passive"))
      (node (ref "DS6") (pin "P9") (pinfunction "VSS_P9") (pintype "passive"))
      (node (ref "DS6") (pin "T1") (pinfunction "VSS_T1") (pintype "passive"))
      (node (ref "DS6") (pin "T9") (pinfunction "VSS_T9") (pintype "passive"))
      (node (ref "DS7") (pin "A9") (pinfunction "VSS_A9") (pintype "passive"))
      (node (ref "DS7") (pin "B1") (pinfunction "VSSQ_B1") (pintype "passive"))
      (node (ref "DS7") (pin "B3") (pinfunction "VSS_B3") (pintype "passive"))
      (node (ref "DS7") (pin "B9") (pinfunction "VSSQ_B9") (pintype "passive"))
      (node (ref "DS7") (pin "D1") (pinfunction "VSSQ_D1") (pintype "passive"))
      (node (ref "DS7") (pin "D8") (pinfunction "VSSQ_D8") (pintype "passive"))
      (node (ref "DS7") (pin "E1") (pinfunction "VSS_E1") (pintype "passive"))
      (node (ref "DS7") (pin "E2") (pinfunction "VSSQ_E2") (pintype "passive"))
      (node (ref "DS7") (pin "E8") (pinfunction "VSSQ_E8") (pintype "passive"))
      (node (ref "DS7") (pin "F9") (pinfunction "VSSQ_F9") (pintype "passive"))
      (node (ref "DS7") (pin "G1") (pinfunction "VSSQ_G1") (pintype "passive"))
      (node (ref "DS7") (pin "G8") (pinfunction "VSS_G8") (pintype "passive"))
      (node (ref "DS7") (pin "G9") (pinfunction "VSSQ_G9") (pintype "passive"))
      (node (ref "DS7") (pin "J2") (pinfunction "VSS_J2") (pintype "passive"))
      (node (ref "DS7") (pin "J8") (pinfunction "VSS_J8") (pintype "passive"))
      (node (ref "DS7") (pin "M1") (pinfunction "VSS_M1") (pintype "passive"))
      (node (ref "DS7") (pin "M9") (pinfunction "VSS_M9") (pintype "passive"))
      (node (ref "DS7") (pin "P1") (pinfunction "VSS_P1") (pintype "passive"))
      (node (ref "DS7") (pin "P9") (pinfunction "VSS_P9") (pintype "passive"))
      (node (ref "DS7") (pin "T1") (pinfunction "VSS_T1") (pintype "passive"))
      (node (ref "DS7") (pin "T9") (pinfunction "VSS_T9") (pintype "passive"))
      (node (ref "DS8") (pin "A9") (pinfunction "VSS_A9") (pintype "passive"))
      (node (ref "DS8") (pin "B1") (pinfunction "VSSQ_B1") (pintype "passive"))
      (node (ref "DS8") (pin "B3") (pinfunction "VSS_B3") (pintype "passive"))
      (node (ref "DS8") (pin "B9") (pinfunction "VSSQ_B9") (pintype "passive"))
      (node (ref "DS8") (pin "D1") (pinfunction "VSSQ_D1") (pintype "passive"))
      (node (ref "DS8") (pin "D8") (pinfunction "VSSQ_D8") (pintype "passive"))
      (node (ref "DS8") (pin "E1") (pinfunction "VSS_E1") (pintype "passive"))
      (node (ref "DS8") (pin "E2") (pinfunction "VSSQ_E2") (pintype "passive"))
      (node (ref "DS8") (pin "E8") (pinfunction "VSSQ_E8") (pintype "passive"))
      (node (ref "DS8") (pin "F9") (pinfunction "VSSQ_F9") (pintype "passive"))
      (node (ref "DS8") (pin "G1") (pinfunction "VSSQ_G1") (pintype "passive"))
      (node (ref "DS8") (pin "G8") (pinfunction "VSS_G8") (pintype "passive"))
      (node (ref "DS8") (pin "G9") (pinfunction "VSSQ_G9") (pintype "passive"))
      (node (ref "DS8") (pin "J2") (pinfunction "VSS_J2") (pintype "passive"))
      (node (ref "DS8") (pin "J8") (pinfunction "VSS_J8") (pintype "passive"))
      (node (ref "DS8") (pin "M1") (pinfunction "VSS_M1") (pintype "passive"))
      (node (ref "DS8") (pin "M9") (pinfunction "VSS_M9") (pintype "passive"))
      (node (ref "DS8") (pin "P1") (pinfunction "VSS_P1") (pintype "passive"))
      (node (ref "DS8") (pin "P9") (pinfunction "VSS_P9") (pintype "passive"))
      (node (ref "DS8") (pin "T1") (pinfunction "VSS_T1") (pintype "passive"))
      (node (ref "DS8") (pin "T9") (pinfunction "VSS_T9") (pintype "passive"))
    )
    (net (code "122") (name "VREF_B") (class "Default")
      (node (ref "DS5") (pin "H1") (pinfunction "VREFDQ_H1") (pintype "passive"))
      (node (ref "DS5") (pin "M8") (pinfunction "VREFCA_M8") (pintype "passive"))
      (node (ref "DS6") (pin "H1") (pinfunction "VREFDQ_H1") (pintype "passive"))
      (node (ref "DS6") (pin "M8") (pinfunction "VREFCA_M8") (pintype "passive"))
      (node (ref "DS7") (pin "H1") (pinfunction "VREFDQ_H1") (pintype "passive"))
      (node (ref "DS7") (pin "M8") (pinfunction "VREFCA_M8") (pintype "passive"))
      (node (ref "DS8") (pin "H1") (pinfunction "VREFDQ_H1") (pintype "passive"))
      (node (ref "DS8") (pin "M8") (pinfunction "VREFCA_M8") (pintype "passive"))
    )
    (net (code "123") (name "unconnected-(DS5-NC-PadJ1)") (class "Default")
      (node (ref "DS5") (pin "J1") (pinfunction "NC_J1") (pintype "passive"))
    )
    (net (code "124") (name "unconnected-(DS5-NC-PadJ9)") (class "Default")
      (node (ref "DS5") (pin "J9") (pinfunction "NC_J9") (pintype "passive"))
    )
    (net (code "125") (name "unconnected-(DS5-NC-PadL1)") (class "Default")
      (node (ref "DS5") (pin "L1") (pinfunction "NC_L1") (pintype "passive"))
    )
    (net (code "126") (name "unconnected-(DS5-NC-PadL9)") (class "Default")
      (node (ref "DS5") (pin "L9") (pinfunction "NC_L9") (pintype "passive"))
    )
    (net (code "127") (name "unconnected-(DS5-NC-PadM7)") (class "Default")
      (node (ref "DS5") (pin "M7") (pinfunction "NC_M7") (pintype "passive"))
    )
    (net (code "128") (name "unconnected-(DS6-NC-PadJ1)") (class "Default")
      (node (ref "DS6") (pin "J1") (pinfunction "NC_J1") (pintype "passive"))
    )
    (net (code "129") (name "unconnected-(DS6-NC-PadJ9)") (class "Default")
      (node (ref "DS6") (pin "J9") (pinfunction "NC_J9") (pintype "passive"))
    )
    (net (code "130") (name "unconnected-(DS6-NC-PadL1)") (class "Default")
      (node (ref "DS6") (pin "L1") (pinfunction "NC_L1") (pintype "passive"))
    )
    (net (code "131") (name "unconnected-(DS6-NC-PadL9)") (class "Default")
      (node (ref "DS6") (pin "L9") (pinfunction "NC_L9") (pintype "passive"))
    )
    (net (code "132") (name "unconnected-(DS6-NC-PadM7)") (class "Default")
      (node (ref "DS6") (pin "M7") (pinfunction "NC_M7") (pintype "passive"))
    )
    (net (code "133") (name "unconnected-(DS7-NC-PadJ1)") (class "Default")
      (node (ref "DS7") (pin "J1") (pinfunction "NC_J1") (pintype "passive"))
    )
    (net (code "134") (name "unconnected-(DS7-NC-PadJ9)") (class "Default")
      (node (ref "DS7") (pin "J9") (pinfunction "NC_J9") (pintype "passive"))
    )
    (net (code "135") (name "unconnected-(DS7-NC-PadL1)") (class "Default")
      (node (ref "DS7") (pin "L1") (pinfunction "NC_L1") (pintype "passive"))
    )
    (net (code "136") (name "unconnected-(DS7-NC-PadL9)") (class "Default")
      (node (ref "DS7") (pin "L9") (pinfunction "NC_L9") (pintype "passive"))
    )
    (net (code "137") (name "unconnected-(DS7-NC-PadM7)") (class "Default")
      (node (ref "DS7") (pin "M7") (pinfunction "NC_M7") (pintype "passive"))
    )
    (net (code "138") (name "unconnected-(DS8-NC-PadJ1)") (class "Default")
      (node (ref "DS8") (pin "J1") (pinfunction "NC_J1") (pintype "passive"))
    )
    (net (code "139") (name "unconnected-(DS8-NC-PadJ9)") (class "Default")
      (node (ref "DS8") (pin "J9") (pinfunction "NC_J9") (pintype "passive"))
    )
    (net (code "140") (name "unconnected-(DS8-NC-PadL1)") (class "Default")
      (node (ref "DS8") (pin "L1") (pinfunction "NC_L1") (pintype "passive"))
    )
    (net (code "141") (name "unconnected-(DS8-NC-PadL9)") (class "Default")
      (node (ref "DS8") (pin "L9") (pinfunction "NC_L9") (pintype "passive"))
    )
    (net (code "142") (name "unconnected-(DS8-NC-PadM7)") (class "Default")
      (node (ref "DS8") (pin "M7") (pinfunction "NC_M7") (pintype "passive"))
    )
  )
)
